# PF9_MIDI.net
KiCad netlist of a schematic drawn in Altium Designer
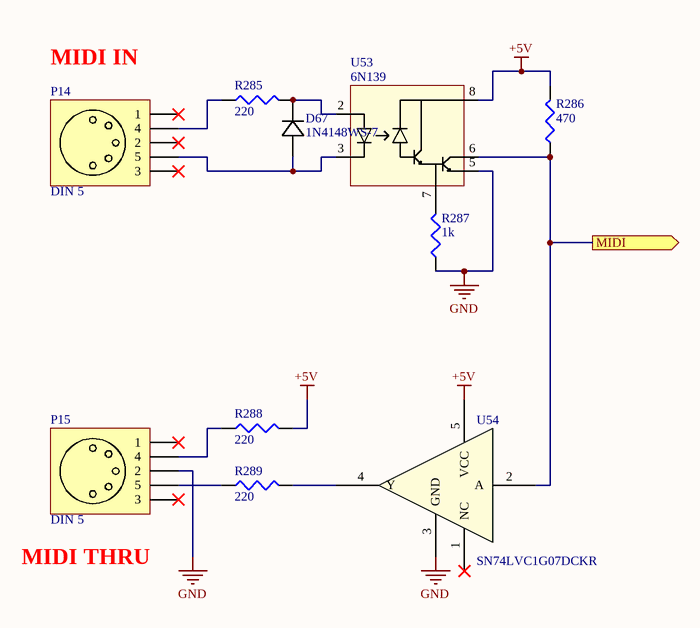
[diagram p0: PF9_MIDI.SchDoc]

(export (version "E")
  (design (tool "Eeschema 10.0.6"))
  (components
    (comp (ref "D67")
      (value "1N4148WS-7")
      (footprint "SOD323-M")
      (description "Diode signaux faibles")
      (libsource (lib "Michel") (part "1N4148WS-7"))
    )
    (comp (ref "P14")
      (value "DIN 5")
      (footprint "PRO SIGNAL_PSG03463")
      (description "DIN 5pin")
      (libsource (lib "Michel") (part "DIN 5pin"))
    )
    (comp (ref "P15")
      (value "DIN 5")
      (footprint "PRO SIGNAL_PSG03463")
      (description "DIN 5pin")
      (libsource (lib "Michel") (part "DIN 5pin"))
    )
    (comp (ref "R285")
      (value "220")
      (footprint "RESC1608X05")
      (description "Resistor")
      (libsource (lib "Michel") (part "Res3"))
    )
    (comp (ref "R286")
      (value "470")
      (footprint "RESC1608X05")
      (description "Resistor")
      (libsource (lib "Michel") (part "Res3"))
    )
    (comp (ref "R287")
      (value "1k")
      (footprint "RESC1608X05")
      (description "Resistor")
      (libsource (lib "Michel") (part "Res3"))
    )
    (comp (ref "R288")
      (value "220")
      (footprint "RESC1608X05")
      (description "Resistor")
      (libsource (lib "Michel") (part "Res3"))
    )
    (comp (ref "R289")
      (value "220")
      (footprint "RESC1608X05")
      (description "Resistor")
      (libsource (lib "Michel") (part "Res3"))
    )
    (comp (ref "U53")
      (value "6N139")
      (footprint "DIP8_VISHAY_6N13")
      (description "Optocoupler")
      (libsource (lib "Michel") (part "6N139"))
    )
    (comp (ref "U54")
      (value "SN74LVC1G07DCKR")
      (footprint "DCK5")
      (description "Buffers & Transmetteurs")
      (libsource (lib "Michel") (part "SN74LVC1G07DCKR"))
    )
  )
  (nets
    (net (code "1") (name "+5V") (class "Default")
      (node (ref "R286") (pin "2") (pinfunction "2_2") (pintype "passive"))
      (node (ref "R288") (pin "2") (pinfunction "2_2") (pintype "passive"))
      (node (ref "U53") (pin "8") (pinfunction "B1_8") (pintype "passive"))
      (node (ref "U54") (pin "5") (pinfunction "VCC_5") (pintype "power_in"))
    )
    (net (code "2") (name "/MIDI") (class "Default")
      (node (ref "R286") (pin "1") (pinfunction "1_1") (pintype "passive"))
      (node (ref "U53") (pin "6") (pinfunction "B1_6") (pintype "passive"))
      (node (ref "U54") (pin "2") (pinfunction "A_2") (pintype "passive"))
    )
    (net (code "3") (name "GND") (class "Default")
      (node (ref "P15") (pin "2") (pinfunction "2_2") (pintype "passive"))
      (node (ref "R287") (pin "1") (pinfunction "1_1") (pintype "passive"))
      (node (ref "U53") (pin "5") (pinfunction "B1_5") (pintype "passive"))
      (node (ref "U54") (pin "3") (pinfunction "GND_3") (pintype "power_in"))
    )
    (net (code "4") (name "Net-(D67-Pad2)") (class "Default")
      (node (ref "D67") (pin "2") (pinfunction "2_2") (pintype "passive"))
      (node (ref "P14") (pin "5") (pinfunction "5_5") (pintype "passive"))
      (node (ref "U53") (pin "3") (pinfunction "B1_3") (pintype "passive"))
    )
    (net (code "5") (name "Net-(P14-Pad4)") (class "Default")
      (node (ref "P14") (pin "4") (pinfunction "4_4") (pintype "passive"))
      (node (ref "R285") (pin "1") (pinfunction "1_1") (pintype "passive"))
    )
    (net (code "6") (name "Net-(P15-Pad4)") (class "Default")
      (node (ref "P15") (pin "4") (pinfunction "4_4") (pintype "passive"))
      (node (ref "R288") (pin "1") (pinfunction "1_1") (pintype "passive"))
    )
    (net (code "7") (name "Net-(P15-Pad5)") (class "Default")
      (node (ref "P15") (pin "5") (pinfunction "5_5") (pintype "passive"))
      (node (ref "R289") (pin "1") (pinfunction "1_1") (pintype "passive"))
    )
    (net (code "8") (name "Net-(R287-Pad2)") (class "Default")
      (node (ref "R287") (pin "2") (pinfunction "2_2") (pintype "passive"))
      (node (ref "U53") (pin "7") (pinfunction "B1_7") (pintype "passive"))
    )
    (net (code "9") (name "Net-(U53-B2)") (class "Default")
      (node (ref "D67") (pin "1") (pinfunction "1_1") (pintype "passive"))
      (node (ref "R285") (pin "2") (pinfunction "2_2") (pintype "passive"))
      (node (ref "U53") (pin "2") (pinfunction "B2_2") (pintype "passive"))
    )
    (net (code "10") (name "Net-(U54-Y)") (class "Default")
      (node (ref "R289") (pin "2") (pinfunction "2_2") (pintype "passive"))
      (node (ref "U54") (pin "4") (pinfunction "Y_4") (pintype "passive"))
    )
    (net (code "11") (name "unconnected-(P14-Pad1)") (class "Default")
      (node (ref "P14") (pin "1") (pinfunction "1_1") (pintype "passive+no_connect"))
    )
    (net (code "12") (name "unconnected-(P14-Pad2)") (class "Default")
      (node (ref "P14") (pin "2") (pinfunction "2_2") (pintype "passive+no_connect"))
    )
    (net (code "13") (name "unconnected-(P14-Pad3)") (class "Default")
      (node (ref "P14") (pin "3") (pinfunction "3_3") (pintype "passive+no_connect"))
    )
    (net (code "14") (name "unconnected-(P15-Pad1)") (class "Default")
      (node (ref "P15") (pin "1") (pinfunction "1_1") (pintype "passive+no_connect"))
    )
    (net (code "15") (name "unconnected-(P15-Pad3)") (class "Default")
      (node (ref "P15") (pin "3") (pinfunction "3_3") (pintype "passive+no_connect"))
    )
    (net (code "16") (name "unconnected-(U54-NC-Pad1)") (class "Default")
      (node (ref "U54") (pin "1") (pinfunction "NC_1") (pintype "passive+no_connect"))
    )
  )
)
